# LB_i6_dimmer-v03_3_3.net
KiCad netlist of a schematic drawn in EAGLE
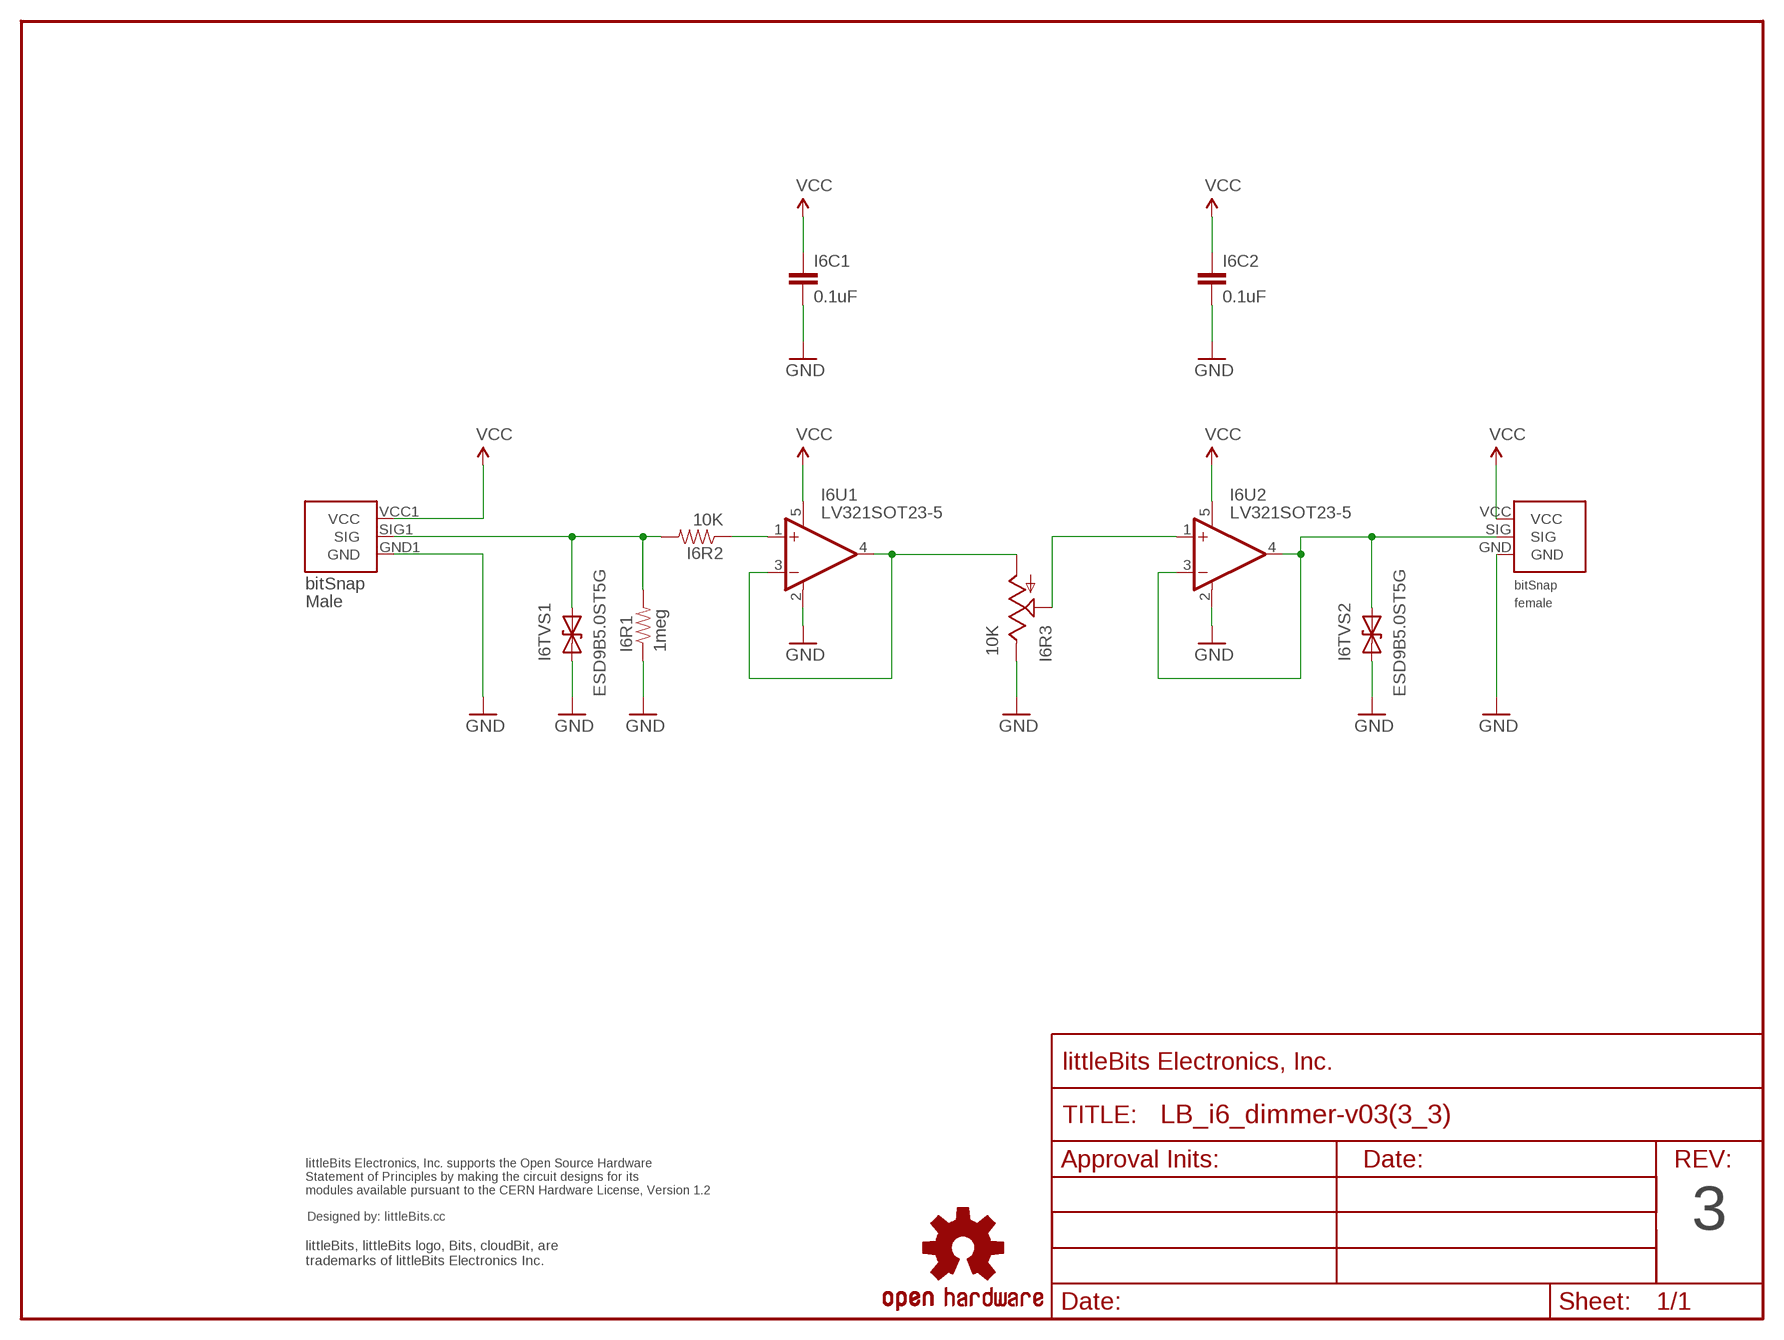
[diagram p0: schematic, sheet 1]

(export (version "E")
  (design (tool "Eeschema 10.0.6"))
  (components
    (comp (ref "FRAME1")
      (value "FRAME-LETTER-OHWOHW")
      (footprint "eagle-import:FABDWG01-OHW")
      (libsource (lib "eagle-import") (part "FRAME-LETTER-OHWOHW"))
    )
    (comp (ref "I6BSF1")
      (value "BITSNAP_V03_FEMALE")
      (footprint "eagle-import:BITSNAP_V03_FEMALE")
      (libsource (lib "eagle-import") (part "BITSNAP_V03_FEMALE"))
    )
    (comp (ref "I6BSM1")
      (value "BITSNAP_V03_MALE")
      (footprint "eagle-import:BITSNAP_V03_MALE")
      (libsource (lib "eagle-import") (part "BITSNAP_V03_MALE"))
    )
    (comp (ref "I6C1")
      (value "0.1uF")
      (footprint "eagle-import:CAP-0603")
      (libsource (lib "eagle-import") (part "CAPCAP-0603"))
    )
    (comp (ref "I6C2")
      (value "0.1uF")
      (footprint "eagle-import:CAP-0603")
      (libsource (lib "eagle-import") (part "CAPCAP-0603"))
    )
    (comp (ref "I6R1")
      (value "1meg")
      (footprint "eagle-import:RES-0603")
      (libsource (lib "eagle-import") (part "RESISTOR0603"))
    )
    (comp (ref "I6R2")
      (value "10K")
      (footprint "eagle-import:RES-0603")
      (libsource (lib "eagle-import") (part "RESISTOR0603"))
    )
    (comp (ref "I6R3")
      (value "10K")
      (footprint "eagle-import:ALPS_POT")
      (libsource (lib "eagle-import") (part "POT"))
    )
    (comp (ref "I6TVS1")
      (value "ESD9B5.0ST5G")
      (footprint "eagle-import:SOD-923")
      (fields (field (name "LB_PN") "?") (field (name "V_CLAMP") "?") (field (name "V_OPERATION") "5V"))
      (libsource (lib "eagle-import") (part "DIODE-TVSSOD-923"))
    )
    (comp (ref "I6TVS2")
      (value "ESD9B5.0ST5G")
      (footprint "eagle-import:SOD-923")
      (fields (field (name "LB_PN") "?") (field (name "V_CLAMP") "?") (field (name "V_OPERATION") "5V"))
      (libsource (lib "eagle-import") (part "DIODE-TVSSOD-923"))
    )
    (comp (ref "I6U1")
      (value "LV321SOT23-5")
      (footprint "eagle-import:SOT23-5")
      (libsource (lib "eagle-import") (part "LV321SOT23-5"))
    )
    (comp (ref "I6U2")
      (value "LV321SOT23-5")
      (footprint "eagle-import:SOT23-5")
      (libsource (lib "eagle-import") (part "LV321SOT23-5"))
    )
    (comp (ref "U$3")
      (value "OSHW-LOGOL")
      (footprint "eagle-import:OSHW-LOGO-L")
      (libsource (lib "eagle-import") (part "OSHW-LOGOL"))
    )
    (comp (ref "U$4")
      (value "LB_CREDITS")
      (footprint "eagle-import:OSHWCREDIT")
      (libsource (lib "eagle-import") (part "LB_CREDITS"))
    )
  )
  (nets
    (net (code "1") (name "GND") (class "Default")
      (node (ref "I6BSF1") (pin "GND") (pinfunction "GND_GND") (pintype "bidirectional"))
      (node (ref "I6BSM1") (pin "GND1") (pinfunction "GND_GND1") (pintype "bidirectional"))
      (node (ref "I6C1") (pin "2") (pinfunction "2_2") (pintype "passive"))
      (node (ref "I6C2") (pin "2") (pinfunction "2_2") (pintype "passive"))
      (node (ref "I6R1") (pin "1") (pinfunction "1_1") (pintype "passive"))
      (node (ref "I6R3") (pin "P$1") (pinfunction "E_P$1") (pintype "passive"))
      (node (ref "I6TVS1") (pin "1") (pinfunction "A_1") (pintype "passive"))
      (node (ref "I6TVS2") (pin "1") (pinfunction "A_1") (pintype "passive"))
      (node (ref "I6U1") (pin "2") (pinfunction "V-_2") (pintype "power_in"))
      (node (ref "I6U2") (pin "2") (pinfunction "V-_2") (pintype "power_in"))
    )
    (net (code "2") (name "Net-(I6BSM1-SIG)") (class "Default")
      (node (ref "I6BSM1") (pin "SIG1") (pinfunction "SIG_SIG1") (pintype "bidirectional"))
      (node (ref "I6R1") (pin "2") (pinfunction "2_2") (pintype "passive"))
      (node (ref "I6R2") (pin "2") (pinfunction "2_2") (pintype "passive"))
      (node (ref "I6TVS1") (pin "2") (pinfunction "C_2") (pintype "passive"))
    )
    (net (code "3") (name "Net-(I6R3-A)") (class "Default")
      (node (ref "I6R3") (pin "P$3") (pinfunction "A_P$3") (pintype "passive"))
      (node (ref "I6U1") (pin "3") (pinfunction "-IN_3") (pintype "input"))
      (node (ref "I6U1") (pin "4") (pinfunction "OUT_4") (pintype "output"))
    )
    (net (code "4") (name "Net-(I6R3-S)") (class "Default")
      (node (ref "I6R3") (pin "P$2") (pinfunction "S_P$2") (pintype "passive"))
      (node (ref "I6U2") (pin "1") (pinfunction "+IN_1") (pintype "input"))
    )
    (net (code "5") (name "Net-(I6TVS2-C)") (class "Default")
      (node (ref "I6BSF1") (pin "SIG") (pinfunction "SIG_SIG") (pintype "bidirectional"))
      (node (ref "I6TVS2") (pin "2") (pinfunction "C_2") (pintype "passive"))
      (node (ref "I6U2") (pin "3") (pinfunction "-IN_3") (pintype "input"))
      (node (ref "I6U2") (pin "4") (pinfunction "OUT_4") (pintype "output"))
    )
    (net (code "6") (name "Net-(I6U1-+IN)") (class "Default")
      (node (ref "I6R2") (pin "1") (pinfunction "1_1") (pintype "passive"))
      (node (ref "I6U1") (pin "1") (pinfunction "+IN_1") (pintype "input"))
    )
    (net (code "7") (name "VCC") (class "Default")
      (node (ref "I6BSF1") (pin "VCC") (pinfunction "VCC_VCC") (pintype "bidirectional"))
      (node (ref "I6BSM1") (pin "VCC1") (pinfunction "VCC_VCC1") (pintype "bidirectional"))
      (node (ref "I6C1") (pin "1") (pinfunction "1_1") (pintype "passive"))
      (node (ref "I6C2") (pin "1") (pinfunction "1_1") (pintype "passive"))
      (node (ref "I6U1") (pin "5") (pinfunction "V+_5") (pintype "power_in"))
      (node (ref "I6U2") (pin "5") (pinfunction "V+_5") (pintype "power_in"))
    )
  )
)
